# PCU_SCH.net
KiCad netlist of a schematic drawn in Altium Designer
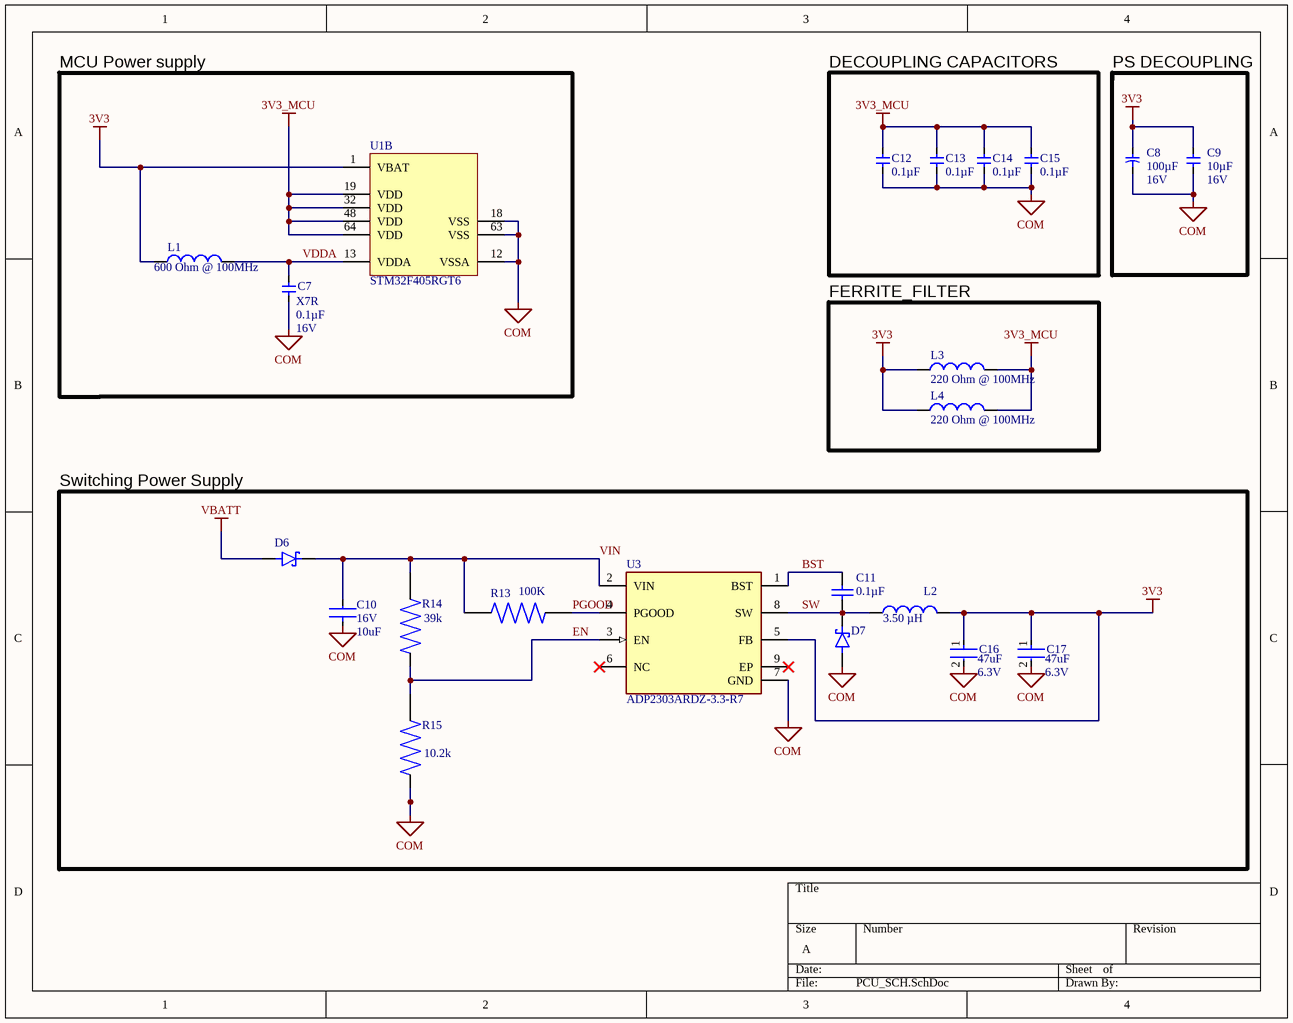
[diagram p0: PCU_SCH.SchDoc]

(export (version "E")
  (design (tool "Eeschema 10.0.6"))
  (components
    (comp (ref "C7")
      (value "GRM188R71C104KA01D")
      (footprint "C0603")
      (description "CAP CER 0.1UF 16V 10% X7R 0603")
      (fields
        (field (name "TOLERANCE") "±10%")
        (field (name "TEMPERATURE COEFFICIENT") "X7R")
        (field (name "CAPACITANCE") "0.1µF")
        (field (name "VOLTAGE - RATED") "16V")
      )
      (libsource (lib "Rockets_2015-2016") (part "GRM188R71C104KA01D"))
    )
    (comp (ref "C8")
      (value "UCL1C101MCL6GS")
      (footprint "SMD J6.3")
      (description "CAP ALUM 100UF 16V 20% SMD")
      (fields
        (field (name "TOLERANCE") "±20%")
        (field (name "CAPACITANCE") "100µF")
        (field (name "VOLTAGE RATING") "16V")
      )
      (libsource (lib "Rockets_2015-2016") (part "UCL1C101MCL6GS"))
    )
    (comp (ref "C9")
      (value "CL21B106KOQNNNE")
      (footprint "C0805")
      (description "CAP CER 10UF 16V 10% X7R 0805")
      (fields
        (field (name "TOLERANCE") "±10%")
        (field (name "CAPACITANCE") "10µF")
        (field (name "VOLTAGE - RATED") "16V")
      )
      (libsource (lib "Rockets_2015-2016") (part "CL21B106KOQNNNE"))
    )
    (comp (ref "C10")
      (value "GRM32ER71H106KA12L")
      (footprint "C1210")
      (description "CAP CER 10UF 16V X7R 0805")
      (fields
        (field (name "MANUFACTURER PART NUMBER") "CL21B106KOQNNNE")
        (field (name "OCTOPART") "https://octopart.com/cl21b106koqnnne-samsung-19832289")
        (field (name "VOLTAGE RATING") "16V")
        (field (name "CAPACITANCE") "10uF")
      )
      (libsource (lib "Altium Content Vault") (part "236180d848d6139a670b325ea6854c9"))
    )
    (comp (ref "C11")
      (value "0.1µF")
      (footprint "CAPC0603X33X15ML03T05")
      (description "MC000311")
      (fields (field (name "MANUFACTURER") "Multicomp"))
      (libsource (lib "Altium Content Vault") (part "CAP"))
    )
    (comp (ref "C12")
      (value "GRM188R71C104KA01D")
      (footprint "C0603")
      (description "CAP CER 0.1UF 16V 10% X7R 0603")
      (fields (field (name "TOLERANCE") "±10%") (field (name "CAPACITANCE") "0.1µF"))
      (libsource (lib "Rockets_2015-2016") (part "GRM188R71C104KA01D"))
    )
    (comp (ref "C13")
      (value "GRM188R71C104KA01D")
      (footprint "C0603")
      (description "CAP CER 0.1UF 16V 10% X7R 0603")
      (fields (field (name "TOLERANCE") "±10%") (field (name "CAPACITANCE") "0.1µF"))
      (libsource (lib "Rockets_2015-2016") (part "GRM188R71C104KA01D"))
    )
    (comp (ref "C14")
      (value "GRM188R71C104KA01D")
      (footprint "C0603")
      (description "CAP CER 0.1UF 16V 10% X7R 0603")
      (fields (field (name "TOLERANCE") "±10%") (field (name "CAPACITANCE") "0.1µF"))
      (libsource (lib "Rockets_2015-2016") (part "GRM188R71C104KA01D"))
    )
    (comp (ref "C15")
      (value "GRM188R71C104KA01D")
      (footprint "C0603")
      (description "CAP CER 0.1UF 16V 10% X7R 0603")
      (fields (field (name "TOLERANCE") "±10%") (field (name "CAPACITANCE") "0.1µF"))
      (libsource (lib "Rockets_2015-2016") (part "GRM188R71C104KA01D"))
    )
    (comp (ref "C16")
      (value "JMK325B7476KMHPR")
      (footprint "FP-1210-L_3_2_0_3-W_2_5_0-MFG")
      (description "CAP CER 47UF 6.3V X7R 1210")
      (fields
        (field (name "TOLERANCE") "10%")
        (field (name "VOLTAGE RATING") "6.3V")
        (field (name "CAPACITANCE") "47uF")
      )
      (libsource (lib "Altium Content Vault") (part "02cd4be3c70576c341d710602a673aa"))
    )
    (comp (ref "C17")
      (value "JMK325B7476KMHPR")
      (footprint "FP-1210-L_3_2_0_3-W_2_5_0-MFG")
      (description "None")
      (fields
        (field (name "TOLERANCE") "10%")
        (field (name "VOLTAGE RATING") "6.3V")
        (field (name "CAPACITANCE") "47uF")
      )
      (libsource (lib "Altium Content Vault") (part "02cd4be3c70576c341d710602a673aa"))
    )
    (comp (ref "D6") (value "SK34A") (footprint "DIOM4325X250N") (libsource (lib "SK34A") (part "SK34A")))
    (comp (ref "D7") (value "SK34A") (footprint "DIOM4325X250N") (libsource (lib "SK34A") (part "SK34A")))
    (comp (ref "L1")
      (value "MMZ1608B601C")
      (footprint "L0603")
      (description "FERRITE CHIP 600 OHM 500MA 0603")
      (fields (field (name "IMPEDANCE @ FREQUENCY") "600 Ohm @ 100MHz"))
      (libsource (lib "Rockets_2015-2016") (part "MMZ1608B601C"))
    )
    (comp (ref "L2")
      (value "7443556350")
      (footprint "WE-HCI-1890")
      (description "SMD Flat Wire High Current Inductor WE-HCI, L=3.50 µH")
      (fields (field (name "INDUCTANCE") "3.50 µH"))
      (libsource (lib "Altium Content Vault") (part "PAS-IND-INDUCTOR-2"))
    )
    (comp (ref "L3")
      (value "BLM21PG221SN1D")
      (footprint "L0805")
      (description "FERRITE CHIP 220 OHM 0805")
      (fields (field (name "IMPEDANCE @ FREQUENCY") "220 Ohm @ 100MHz"))
      (libsource (lib "Rockets_2015-2016") (part "BLM21PG221SN1D"))
    )
    (comp (ref "L4")
      (value "BLM21PG221SN1D")
      (footprint "L0805")
      (description "FERRITE CHIP 220 OHM 0805")
      (fields (field (name "IMPEDANCE @ FREQUENCY") "220 Ohm @ 100MHz"))
      (libsource (lib "Rockets_2015-2016") (part "BLM21PG221SN1D"))
    )
    (comp (ref "R13")
      (value "100K")
      (footprint "RES_ERJU03J104V")
      (description "RES 100K OHM 5% 1/10W 0603 SMD")
      (fields (field (name "MP") "ERJU03J104V"))
      (libsource (lib "ERJU03J104V") (part "ERJU03J104V"))
    )
    (comp (ref "R14")
      (value "39k")
      (footprint "RESC1608X55N")
      (description "Res Thick Film 0603 39K Ohm 5% 0.1W(1/10W) ?200ppm/?C Molded SMD Automotive T/R")
      (fields (field (name "MP") "ERJ-3GEYJ393V"))
      (libsource (lib "ERJ-3GEYJ393V") (part "ERJ-3GEYJ393V"))
    )
    (comp (ref "R15")
      (value "10.2k")
      (footprint "RES_ERJ3EKF1022V")
      (description "RES SMD 10.2K OHM 1% 1/10W 0603")
      (fields (field (name "MP") "ERJ3EKF1022V"))
      (libsource (lib "ERJ3EKF1022V") (part "ERJ3EKF1022V"))
    )
    (comp (ref "U1")
      (value "STM32F405RGT6")
      (footprint "STM-LQFP64_M")
      (fields (field (name "MANUFACTURER") "STMicroelectronics"))
      (libsource (lib "Altium Content Vault") (part "MC-ARM-STM32F4X5-SQ64"))
    )
    (comp (ref "U3")
      (value "ADP2303ARDZ-3.3-R7")
      (footprint "FP-RD-8-1-IPC_A")
      (description "IC REG BUCK 3.3V 3A 8SOIC")
      (libsource (lib "Altium Content Vault") (part "27afd87f0f308fe437871902fcc7daa"))
    )
  )
  (nets
    (net (code "1") (name "/BST") (class "Default")
      (node (ref "C11") (pin "2") (pinfunction "2_2") (pintype "passive"))
      (node (ref "U3") (pin "1") (pinfunction "BST_1") (pintype "passive"))
    )
    (net (code "2") (name "/EN") (class "Default")
      (node (ref "R14") (pin "1") (pinfunction "1_1") (pintype "passive"))
      (node (ref "R15") (pin "2") (pinfunction "2_2") (pintype "passive"))
      (node (ref "U3") (pin "3") (pinfunction "EN_3") (pintype "input"))
    )
    (net (code "3") (name "/PGOOD") (class "Default")
      (node (ref "R13") (pin "2") (pinfunction "2_2") (pintype "passive"))
      (node (ref "U3") (pin "4") (pinfunction "PGOOD_4") (pintype "passive"))
    )
    (net (code "4") (name "/SW") (class "Default")
      (node (ref "C11") (pin "1") (pinfunction "1_1") (pintype "passive"))
      (node (ref "D7") (pin "C") (pinfunction "K_C") (pintype "passive"))
      (node (ref "L2") (pin "1") (pinfunction "1_1") (pintype "passive"))
      (node (ref "U3") (pin "8") (pinfunction "SW_8") (pintype "passive"))
    )
    (net (code "5") (name "/VDDA") (class "Default")
      (node (ref "C7") (pin "2") (pinfunction "2_2") (pintype "passive"))
      (node (ref "L1") (pin "2") (pinfunction "2_2") (pintype "passive"))
      (node (ref "U1") (pin "13") (pinfunction "VDDA_13") (pintype "power_in"))
    )
    (net (code "6") (name "/VIN") (class "Default")
      (node (ref "C10") (pin "2") (pinfunction "2_2") (pintype "passive"))
      (node (ref "D6") (pin "C") (pinfunction "K_C") (pintype "passive"))
      (node (ref "R13") (pin "1") (pinfunction "1_1") (pintype "passive"))
      (node (ref "R14") (pin "2") (pinfunction "2_2") (pintype "passive"))
      (node (ref "U3") (pin "2") (pinfunction "VIN_2") (pintype "power_in"))
    )
    (net (code "7") (name "3V3") (class "Default")
      (node (ref "C16") (pin "1") (pinfunction "1_1") (pintype "passive"))
      (node (ref "C17") (pin "1") (pinfunction "1_1") (pintype "passive"))
      (node (ref "C8") (pin "A") (pinfunction "A_A") (pintype "passive"))
      (node (ref "C9") (pin "2") (pinfunction "2_2") (pintype "passive"))
      (node (ref "L1") (pin "1") (pinfunction "1_1") (pintype "passive"))
      (node (ref "L2") (pin "2") (pinfunction "2_2") (pintype "passive"))
      (node (ref "L3") (pin "1") (pinfunction "1_1") (pintype "passive"))
      (node (ref "L4") (pin "1") (pinfunction "1_1") (pintype "passive"))
      (node (ref "U1") (pin "1") (pinfunction "VBAT_1") (pintype "power_in"))
      (node (ref "U3") (pin "5") (pinfunction "FB_5") (pintype "passive"))
    )
    (net (code "8") (name "3V3_MCU") (class "Default")
      (node (ref "C12") (pin "1") (pinfunction "1_1") (pintype "passive"))
      (node (ref "C13") (pin "1") (pinfunction "1_1") (pintype "passive"))
      (node (ref "C14") (pin "1") (pinfunction "1_1") (pintype "passive"))
      (node (ref "C15") (pin "1") (pinfunction "1_1") (pintype "passive"))
      (node (ref "L3") (pin "2") (pinfunction "2_2") (pintype "passive"))
      (node (ref "L4") (pin "2") (pinfunction "2_2") (pintype "passive"))
      (node (ref "U1") (pin "19") (pinfunction "VDD_19") (pintype "power_in"))
      (node (ref "U1") (pin "32") (pinfunction "VDD_32") (pintype "power_in"))
      (node (ref "U1") (pin "48") (pinfunction "VDD_48") (pintype "power_in"))
      (node (ref "U1") (pin "64") (pinfunction "VDD_64") (pintype "power_in"))
    )
    (net (code "9") (name "COM") (class "Default")
      (node (ref "C10") (pin "1") (pinfunction "1_1") (pintype "passive"))
      (node (ref "C12") (pin "2") (pinfunction "2_2") (pintype "passive"))
      (node (ref "C13") (pin "2") (pinfunction "2_2") (pintype "passive"))
      (node (ref "C14") (pin "2") (pinfunction "2_2") (pintype "passive"))
      (node (ref "C15") (pin "2") (pinfunction "2_2") (pintype "passive"))
      (node (ref "C16") (pin "2") (pinfunction "2_2") (pintype "passive"))
      (node (ref "C17") (pin "2") (pinfunction "2_2") (pintype "passive"))
      (node (ref "C7") (pin "1") (pinfunction "1_1") (pintype "passive"))
      (node (ref "C8") (pin "K") (pinfunction "K_K") (pintype "passive"))
      (node (ref "C9") (pin "1") (pinfunction "1_1") (pintype "passive"))
      (node (ref "D7") (pin "A") (pinfunction "A_A") (pintype "passive"))
      (node (ref "R15") (pin "1") (pinfunction "1_1") (pintype "passive"))
      (node (ref "U1") (pin "12") (pinfunction "VSSA_12") (pintype "power_in"))
      (node (ref "U1") (pin "18") (pinfunction "VSS_18") (pintype "power_in"))
      (node (ref "U1") (pin "63") (pinfunction "VSS_63") (pintype "power_in"))
      (node (ref "U3") (pin "7") (pinfunction "GND_7") (pintype "power_in"))
    )
    (net (code "10") (name "VBATT") (class "Default")
      (node (ref "D6") (pin "A") (pinfunction "A_A") (pintype "passive"))
    )
    (net (code "11") (name "unconnected-(U3-EP-Pad9)") (class "Default")
      (node (ref "U3") (pin "9") (pinfunction "EP_9") (pintype "power_in+no_connect"))
    )
    (net (code "12") (name "unconnected-(U3-NC-Pad6)") (class "Default")
      (node (ref "U3") (pin "6") (pinfunction "NC_6") (pintype "passive+no_connect"))
    )
  )
)
